# OLED_Board.net
KiCad netlist of a schematic drawn in Altium Designer
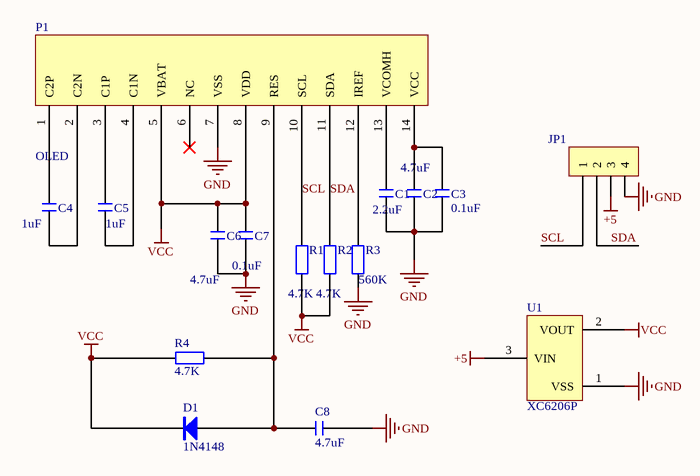
[diagram p0: OLED_Board.SchDoc]

(export (version "E")
  (design (tool "Eeschema 10.0.6"))
  (components
    (comp (ref "C1")
      (value "2.2uF")
      (footprint "C 0603_L")
      (description "无极性贴片电容")
      (libsource (lib "电容-电阻-电感-电位器") (part "C"))
    )
    (comp (ref "C2")
      (value "4.7uF")
      (footprint "C 0603_L")
      (description "无极性贴片电容")
      (libsource (lib "电容-电阻-电感-电位器") (part "C"))
    )
    (comp (ref "C3")
      (value "0.1uF")
      (footprint "C 0603_L")
      (description "无极性贴片电容")
      (libsource (lib "电容-电阻-电感-电位器") (part "C"))
    )
    (comp (ref "C4")
      (value "1uF")
      (footprint "C 0603_L")
      (description "无极性贴片电容")
      (libsource (lib "电容-电阻-电感-电位器") (part "C"))
    )
    (comp (ref "C5")
      (value "1uF")
      (footprint "C 0603_L")
      (description "无极性贴片电容")
      (libsource (lib "电容-电阻-电感-电位器") (part "C"))
    )
    (comp (ref "C6")
      (value "4.7uF")
      (footprint "C 0603_L")
      (description "无极性贴片电容")
      (libsource (lib "电容-电阻-电感-电位器") (part "C"))
    )
    (comp (ref "C7")
      (value "0.1uF")
      (footprint "C 0603_L")
      (description "无极性贴片电容")
      (libsource (lib "电容-电阻-电感-电位器") (part "C"))
    )
    (comp (ref "C8")
      (value "4.7uF")
      (footprint "C 0603_L")
      (description "无极性贴片电容")
      (libsource (lib "电容-电阻-电感-电位器") (part "C"))
    )
    (comp (ref "D1")
      (value "1N4148")
      (footprint "MINI_MELF (LL34)")
      (description "高速开关二极管")
      (libsource (lib "二极管-整流桥") (part "1N4148"))
    )
    (comp (ref "JP1")
      (value "HDR-1X4")
      (footprint "XH2.54-LI-4P")
      (description "4P接插件")
      (libsource (lib "XH2.54") (part "Header 4"))
    )
    (comp (ref "P1") (value "OLED") (footprint "OLED") (libsource (lib "OLED") (part "OLED")))
    (comp (ref "R1")
      (value "4.7K")
      (footprint "R 0603_L")
      (description "贴片电阻")
      (libsource (lib "电容-电阻-电感-电位器") (part "R"))
    )
    (comp (ref "R2")
      (value "4.7K")
      (footprint "R 0603_L")
      (description "贴片电阻")
      (libsource (lib "电容-电阻-电感-电位器") (part "R"))
    )
    (comp (ref "R3")
      (value "560K")
      (footprint "R 0603_L")
      (description "贴片电阻")
      (libsource (lib "电容-电阻-电感-电位器") (part "R"))
    )
    (comp (ref "R4")
      (value "4.7K")
      (footprint "R 0603_L")
      (description "贴片电阻")
      (libsource (lib "电容-电阻-电感-电位器") (part "R"))
    )
    (comp (ref "U1") (value "XC6206P") (footprint "SOT23-3M") (libsource (lib "OLED") (part "XC6206P")))
  )
  (nets
    (net (code "1") (name "+5") (class "Default")
      (node (ref "JP1") (pin "3") (pinfunction "3_3") (pintype "passive"))
      (node (ref "U1") (pin "3") (pinfunction "VIN_3") (pintype "passive"))
    )
    (net (code "2") (name "/SCL") (class "Default")
      (node (ref "JP1") (pin "1") (pinfunction "1_1") (pintype "passive"))
      (node (ref "P1") (pin "10") (pinfunction "SCL_10") (pintype "passive"))
      (node (ref "R1") (pin "2") (pinfunction "2_2") (pintype "passive"))
    )
    (net (code "3") (name "/SDA") (class "Default")
      (node (ref "JP1") (pin "2") (pinfunction "2_2") (pintype "passive"))
      (node (ref "P1") (pin "11") (pinfunction "SDA_11") (pintype "passive"))
      (node (ref "R2") (pin "2") (pinfunction "2_2") (pintype "passive"))
    )
    (net (code "4") (name "GND") (class "Default")
      (node (ref "C1") (pin "1") (pinfunction "1_1") (pintype "passive"))
      (node (ref "C2") (pin "1") (pinfunction "1_1") (pintype "passive"))
      (node (ref "C3") (pin "1") (pinfunction "1_1") (pintype "passive"))
      (node (ref "C6") (pin "1") (pinfunction "1_1") (pintype "passive"))
      (node (ref "C7") (pin "1") (pinfunction "1_1") (pintype "passive"))
      (node (ref "C8") (pin "2") (pinfunction "2_2") (pintype "passive"))
      (node (ref "JP1") (pin "4") (pinfunction "4_4") (pintype "passive"))
      (node (ref "P1") (pin "7") (pinfunction "VSS_7") (pintype "passive"))
      (node (ref "R3") (pin "1") (pinfunction "1_1") (pintype "passive"))
      (node (ref "U1") (pin "1") (pinfunction "VSS_1") (pintype "passive"))
    )
    (net (code "5") (name "Net-(D1-A)") (class "Default")
      (node (ref "C8") (pin "1") (pinfunction "1_1") (pintype "passive"))
      (node (ref "D1") (pin "1") (pinfunction "A_1") (pintype "passive"))
      (node (ref "P1") (pin "9") (pinfunction "RES_9") (pintype "passive"))
      (node (ref "R4") (pin "2") (pinfunction "2_2") (pintype "passive"))
    )
    (net (code "6") (name "Net-(P1-C1N)") (class "Default")
      (node (ref "C5") (pin "1") (pinfunction "1_1") (pintype "passive"))
      (node (ref "P1") (pin "4") (pinfunction "C1N_4") (pintype "passive"))
    )
    (net (code "7") (name "Net-(P1-C1P)") (class "Default")
      (node (ref "C5") (pin "2") (pinfunction "2_2") (pintype "passive"))
      (node (ref "P1") (pin "3") (pinfunction "C1P_3") (pintype "passive"))
    )
    (net (code "8") (name "Net-(P1-C2N)") (class "Default")
      (node (ref "C4") (pin "1") (pinfunction "1_1") (pintype "passive"))
      (node (ref "P1") (pin "2") (pinfunction "C2N_2") (pintype "passive"))
    )
    (net (code "9") (name "Net-(P1-C2P)") (class "Default")
      (node (ref "C4") (pin "2") (pinfunction "2_2") (pintype "passive"))
      (node (ref "P1") (pin "1") (pinfunction "C2P_1") (pintype "passive"))
    )
    (net (code "10") (name "Net-(P1-IREF)") (class "Default")
      (node (ref "P1") (pin "12") (pinfunction "IREF_12") (pintype "passive"))
      (node (ref "R3") (pin "2") (pinfunction "2_2") (pintype "passive"))
    )
    (net (code "11") (name "Net-(P1-VCC)") (class "Default")
      (node (ref "C2") (pin "2") (pinfunction "2_2") (pintype "passive"))
      (node (ref "C3") (pin "2") (pinfunction "2_2") (pintype "passive"))
      (node (ref "P1") (pin "14") (pinfunction "VCC_14") (pintype "passive"))
    )
    (net (code "12") (name "Net-(P1-VCOMH)") (class "Default")
      (node (ref "C1") (pin "2") (pinfunction "2_2") (pintype "passive"))
      (node (ref "P1") (pin "13") (pinfunction "VCOMH_13") (pintype "passive"))
    )
    (net (code "13") (name "VCC") (class "Default")
      (node (ref "C6") (pin "2") (pinfunction "2_2") (pintype "passive"))
      (node (ref "C7") (pin "2") (pinfunction "2_2") (pintype "passive"))
      (node (ref "D1") (pin "2") (pinfunction "K_2") (pintype "passive"))
      (node (ref "P1") (pin "5") (pinfunction "VBAT_5") (pintype "passive"))
      (node (ref "P1") (pin "8") (pinfunction "VDD_8") (pintype "passive"))
      (node (ref "R1") (pin "1") (pinfunction "1_1") (pintype "passive"))
      (node (ref "R2") (pin "1") (pinfunction "1_1") (pintype "passive"))
      (node (ref "R4") (pin "1") (pinfunction "1_1") (pintype "passive"))
      (node (ref "U1") (pin "2") (pinfunction "VOUT_2") (pintype "passive"))
    )
    (net (code "14") (name "unconnected-(P1-NC-Pad6)") (class "Default")
      (node (ref "P1") (pin "6") (pinfunction "NC_6") (pintype "passive+no_connect"))
    )
  )
)
